# Motor.net
KiCad netlist of a schematic drawn in Altium Designer
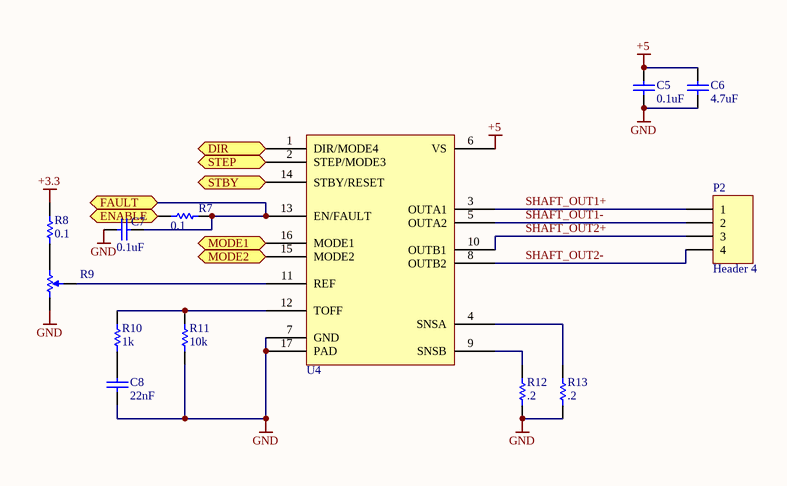
[diagram p0: Motor.SchDoc]

(export (version "E")
  (design (tool "Eeschema 10.0.6"))
  (components
    (comp (ref "C5")
      (value "0.1uF")
      (footprint "CAPC1608X94X35LL15T15")
      (description "CAP .1UF 16V CERAMIC X7R 0603")
      (fields
        (field (name "MANUFACTURER") "Yageo")
        (field (name "MANUFACTURER PART NUMBER") "CC0603KRX7R7BB105")
      )
      (libsource (lib "Altium Content Vault") (part "CAP-NP-2"))
    )
    (comp (ref "C6")
      (value "4.7uF")
      (footprint "CAPC0603(1608)55_M")
      (description "CAP 4.7uF 6.3V ±10% 0603 (1608 Metric) Thickness 0.55mm SMD")
      (fields (field (name "TOLERANCE") "Â±10%") (field (name "MANUFACTURER") "KEMET"))
      (libsource (lib "Altium Content Vault") (part "CAP"))
    )
    (comp (ref "C7")
      (value "0.1uF")
      (footprint "CAPC1608X94X35LL15T15")
      (description "CAP .1UF 16V CERAMIC X7R 0603")
      (fields
        (field (name "MANUFACTURER") "Yageo")
        (field (name "MANUFACTURER PART NUMBER") "CC0603KRX7R7BB105")
      )
      (libsource (lib "Altium Content Vault") (part "CAP-NP-2"))
    )
    (comp (ref "C8")
      (value "22nF")
      (footprint "CAPC1608X94X35LL15T15")
      (description "CAP .1UF 16V CERAMIC X7R 0603")
      (fields
        (field (name "MANUFACTURER") "Yageo")
        (field (name "MANUFACTURER PART NUMBER") "CC0603KRX7R7BB105")
      )
      (libsource (lib "Altium Content Vault") (part "CMP-1661-00001-2"))
    )
    (comp (ref "P2")
      (value "Header 4")
      (footprint "HDR1X4")
      (description "Header, 4-Pin")
      (fields (field (name "PUBLISHER") "Altium Limited"))
      (libsource (lib "Miscellaneous Connectors") (part "Header 4"))
    )
    (comp (ref "R7")
      (value "0.1")
      (footprint "RESC0603(1608)_N")
      (description "0R12 0.1W 1% 0603 (1608 Metric)  SMD")
      (fields (field (name "POWER") "0.1 W") (field (name "TOLERANCE") "1 %"))
      (libsource (lib "Altium Content Vault") (part "RES"))
    )
    (comp (ref "R8")
      (value "0.1")
      (footprint "RESC0603(1608)_N")
      (description "0R12 0.1W 1% 0603 (1608 Metric)  SMD")
      (fields (field (name "POWER") "0.1 W") (field (name "TOLERANCE") "1 %"))
      (libsource (lib "Altium Content Vault") (part "RES"))
    )
    (comp (ref "R9")
      (value "3313J-1-503E")
      (footprint "BOUR-3313J-1_V")
      (fields (field (name "MANUFACTURER") "Bourns"))
      (libsource (lib "Altium Content Vault") (part "CMP-2000-05588-1"))
    )
    (comp (ref "R10")
      (value "1k")
      (footprint "RESC0603(1608)_N")
      (description "0R12 0.1W 1% 0603 (1608 Metric)  SMD")
      (fields (field (name "POWER") "0.1 W") (field (name "TOLERANCE") "1 %"))
      (libsource (lib "Altium Content Vault") (part "RES"))
    )
    (comp (ref "R11")
      (value "10k")
      (footprint "RESC0603(1608)_N")
      (description "0R12 0.1W 1% 0603 (1608 Metric)  SMD")
      (fields (field (name "POWER") "0.1 W") (field (name "TOLERANCE") "1 %"))
      (libsource (lib "Altium Content Vault") (part "RES"))
    )
    (comp (ref "R12")
      (value ".2")
      (footprint "RESC0603(1608)_N")
      (description "0R12 0.1W 1% 0603 (1608 Metric)  SMD")
      (fields (field (name "POWER") "0.1 W") (field (name "TOLERANCE") "1 %"))
      (libsource (lib "Altium Content Vault") (part "CMP-1012-00511-1"))
    )
    (comp (ref "R13")
      (value ".2")
      (footprint "RESC0603(1608)_N")
      (description "0R12 0.1W 1% 0603 (1608 Metric)  SMD")
      (fields (field (name "POWER") "0.1 W") (field (name "TOLERANCE") "1 %"))
      (libsource (lib "Altium Content Vault") (part "RES"))
    )
    (comp (ref "U4")
      (value "STSPIN220")
      (footprint "STSPIN220-QFN127P600-8N")
      (libsource (lib "ZLS_Schematic_lib") (part "STSPIN220"))
    )
  )
  (nets
    (net (code "1") (name "+3.3") (class "Default")
      (node (ref "R8") (pin "2") (pinfunction "2_2") (pintype "passive"))
    )
    (net (code "2") (name "+5") (class "Default")
      (node (ref "C5") (pin "1") (pinfunction "1_1") (pintype "passive"))
      (node (ref "C6") (pin "2") (pinfunction "2_2") (pintype "passive"))
      (node (ref "U4") (pin "6") (pinfunction "VS_6") (pintype "passive"))
    )
    (net (code "3") (name "/DIR") (class "Default")
      (node (ref "U4") (pin "1") (pinfunction "DIR/MODE4_1") (pintype "passive"))
    )
    (net (code "4") (name "/ENABLE") (class "Default")
      (node (ref "R7") (pin "2") (pinfunction "2_2") (pintype "passive"))
    )
    (net (code "5") (name "/FAULT") (class "Default")
      (node (ref "C7") (pin "2") (pinfunction "2_2") (pintype "passive"))
      (node (ref "R7") (pin "1") (pinfunction "1_1") (pintype "passive"))
      (node (ref "U4") (pin "13") (pinfunction "EN/FAULT_13") (pintype "passive"))
    )
    (net (code "6") (name "/MODE1") (class "Default")
      (node (ref "U4") (pin "16") (pinfunction "MODE1_16") (pintype "passive"))
    )
    (net (code "7") (name "/MODE2") (class "Default")
      (node (ref "U4") (pin "15") (pinfunction "MODE2_15") (pintype "passive"))
    )
    (net (code "8") (name "/SHAFT_OUT1+") (class "Default")
      (node (ref "P2") (pin "1") (pinfunction "1_1") (pintype "passive"))
      (node (ref "U4") (pin "3") (pinfunction "OUTA1_3") (pintype "passive"))
    )
    (net (code "9") (name "/SHAFT_OUT1-") (class "Default")
      (node (ref "P2") (pin "2") (pinfunction "2_2") (pintype "passive"))
      (node (ref "U4") (pin "5") (pinfunction "OUTA2_5") (pintype "passive"))
    )
    (net (code "10") (name "/SHAFT_OUT2+") (class "Default")
      (node (ref "P2") (pin "3") (pinfunction "3_3") (pintype "passive"))
      (node (ref "U4") (pin "10") (pinfunction "OUTB1_10") (pintype "passive"))
    )
    (net (code "11") (name "/SHAFT_OUT2-") (class "Default")
      (node (ref "P2") (pin "4") (pinfunction "4_4") (pintype "passive"))
      (node (ref "U4") (pin "8") (pinfunction "OUTB2_8") (pintype "passive"))
    )
    (net (code "12") (name "/STBY") (class "Default")
      (node (ref "U4") (pin "14") (pinfunction "STBY/RESET_14") (pintype "passive"))
    )
    (net (code "13") (name "/STEP") (class "Default")
      (node (ref "U4") (pin "2") (pinfunction "STEP/MODE3_2") (pintype "passive"))
    )
    (net (code "14") (name "GND") (class "Default")
      (node (ref "C5") (pin "2") (pinfunction "2_2") (pintype "passive"))
      (node (ref "C6") (pin "1") (pinfunction "1_1") (pintype "passive"))
      (node (ref "C7") (pin "1") (pinfunction "1_1") (pintype "passive"))
      (node (ref "C8") (pin "2") (pinfunction "2_2") (pintype "passive"))
      (node (ref "R11") (pin "1") (pinfunction "1_1") (pintype "passive"))
      (node (ref "R12") (pin "1") (pinfunction "1_1") (pintype "passive"))
      (node (ref "R13") (pin "1") (pinfunction "1_1") (pintype "passive"))
      (node (ref "R9") (pin "1") (pinfunction "1_1") (pintype "passive"))
      (node (ref "U4") (pin "17") (pinfunction "PAD_17") (pintype "passive"))
      (node (ref "U4") (pin "7") (pinfunction "GND_7") (pintype "passive"))
    )
    (net (code "15") (name "Net-(C8-Pad1)") (class "Default")
      (node (ref "C8") (pin "1") (pinfunction "1_1") (pintype "passive"))
      (node (ref "R10") (pin "1") (pinfunction "1_1") (pintype "passive"))
    )
    (net (code "16") (name "Net-(R8-Pad1)") (class "Default")
      (node (ref "R8") (pin "1") (pinfunction "1_1") (pintype "passive"))
      (node (ref "R9") (pin "3") (pinfunction "3_3") (pintype "passive"))
    )
    (net (code "17") (name "Net-(U4-REF)") (class "Default")
      (node (ref "R9") (pin "2") (pinfunction "2_2") (pintype "passive"))
      (node (ref "U4") (pin "11") (pinfunction "REF_11") (pintype "passive"))
    )
    (net (code "18") (name "Net-(U4-SNSA)") (class "Default")
      (node (ref "R13") (pin "2") (pinfunction "2_2") (pintype "passive"))
      (node (ref "U4") (pin "4") (pinfunction "SNSA_4") (pintype "passive"))
    )
    (net (code "19") (name "Net-(U4-SNSB)") (class "Default")
      (node (ref "R12") (pin "2") (pinfunction "2_2") (pintype "passive"))
      (node (ref "U4") (pin "9") (pinfunction "SNSB_9") (pintype "passive"))
    )
    (net (code "20") (name "Net-(U4-TOFF)") (class "Default")
      (node (ref "R10") (pin "2") (pinfunction "2_2") (pintype "passive"))
      (node (ref "R11") (pin "2") (pinfunction "2_2") (pintype "passive"))
      (node (ref "U4") (pin "12") (pinfunction "TOFF_12") (pintype "passive"))
    )
  )
)
